# Communication_Management.net
KiCad netlist of a schematic drawn in Altium Designer
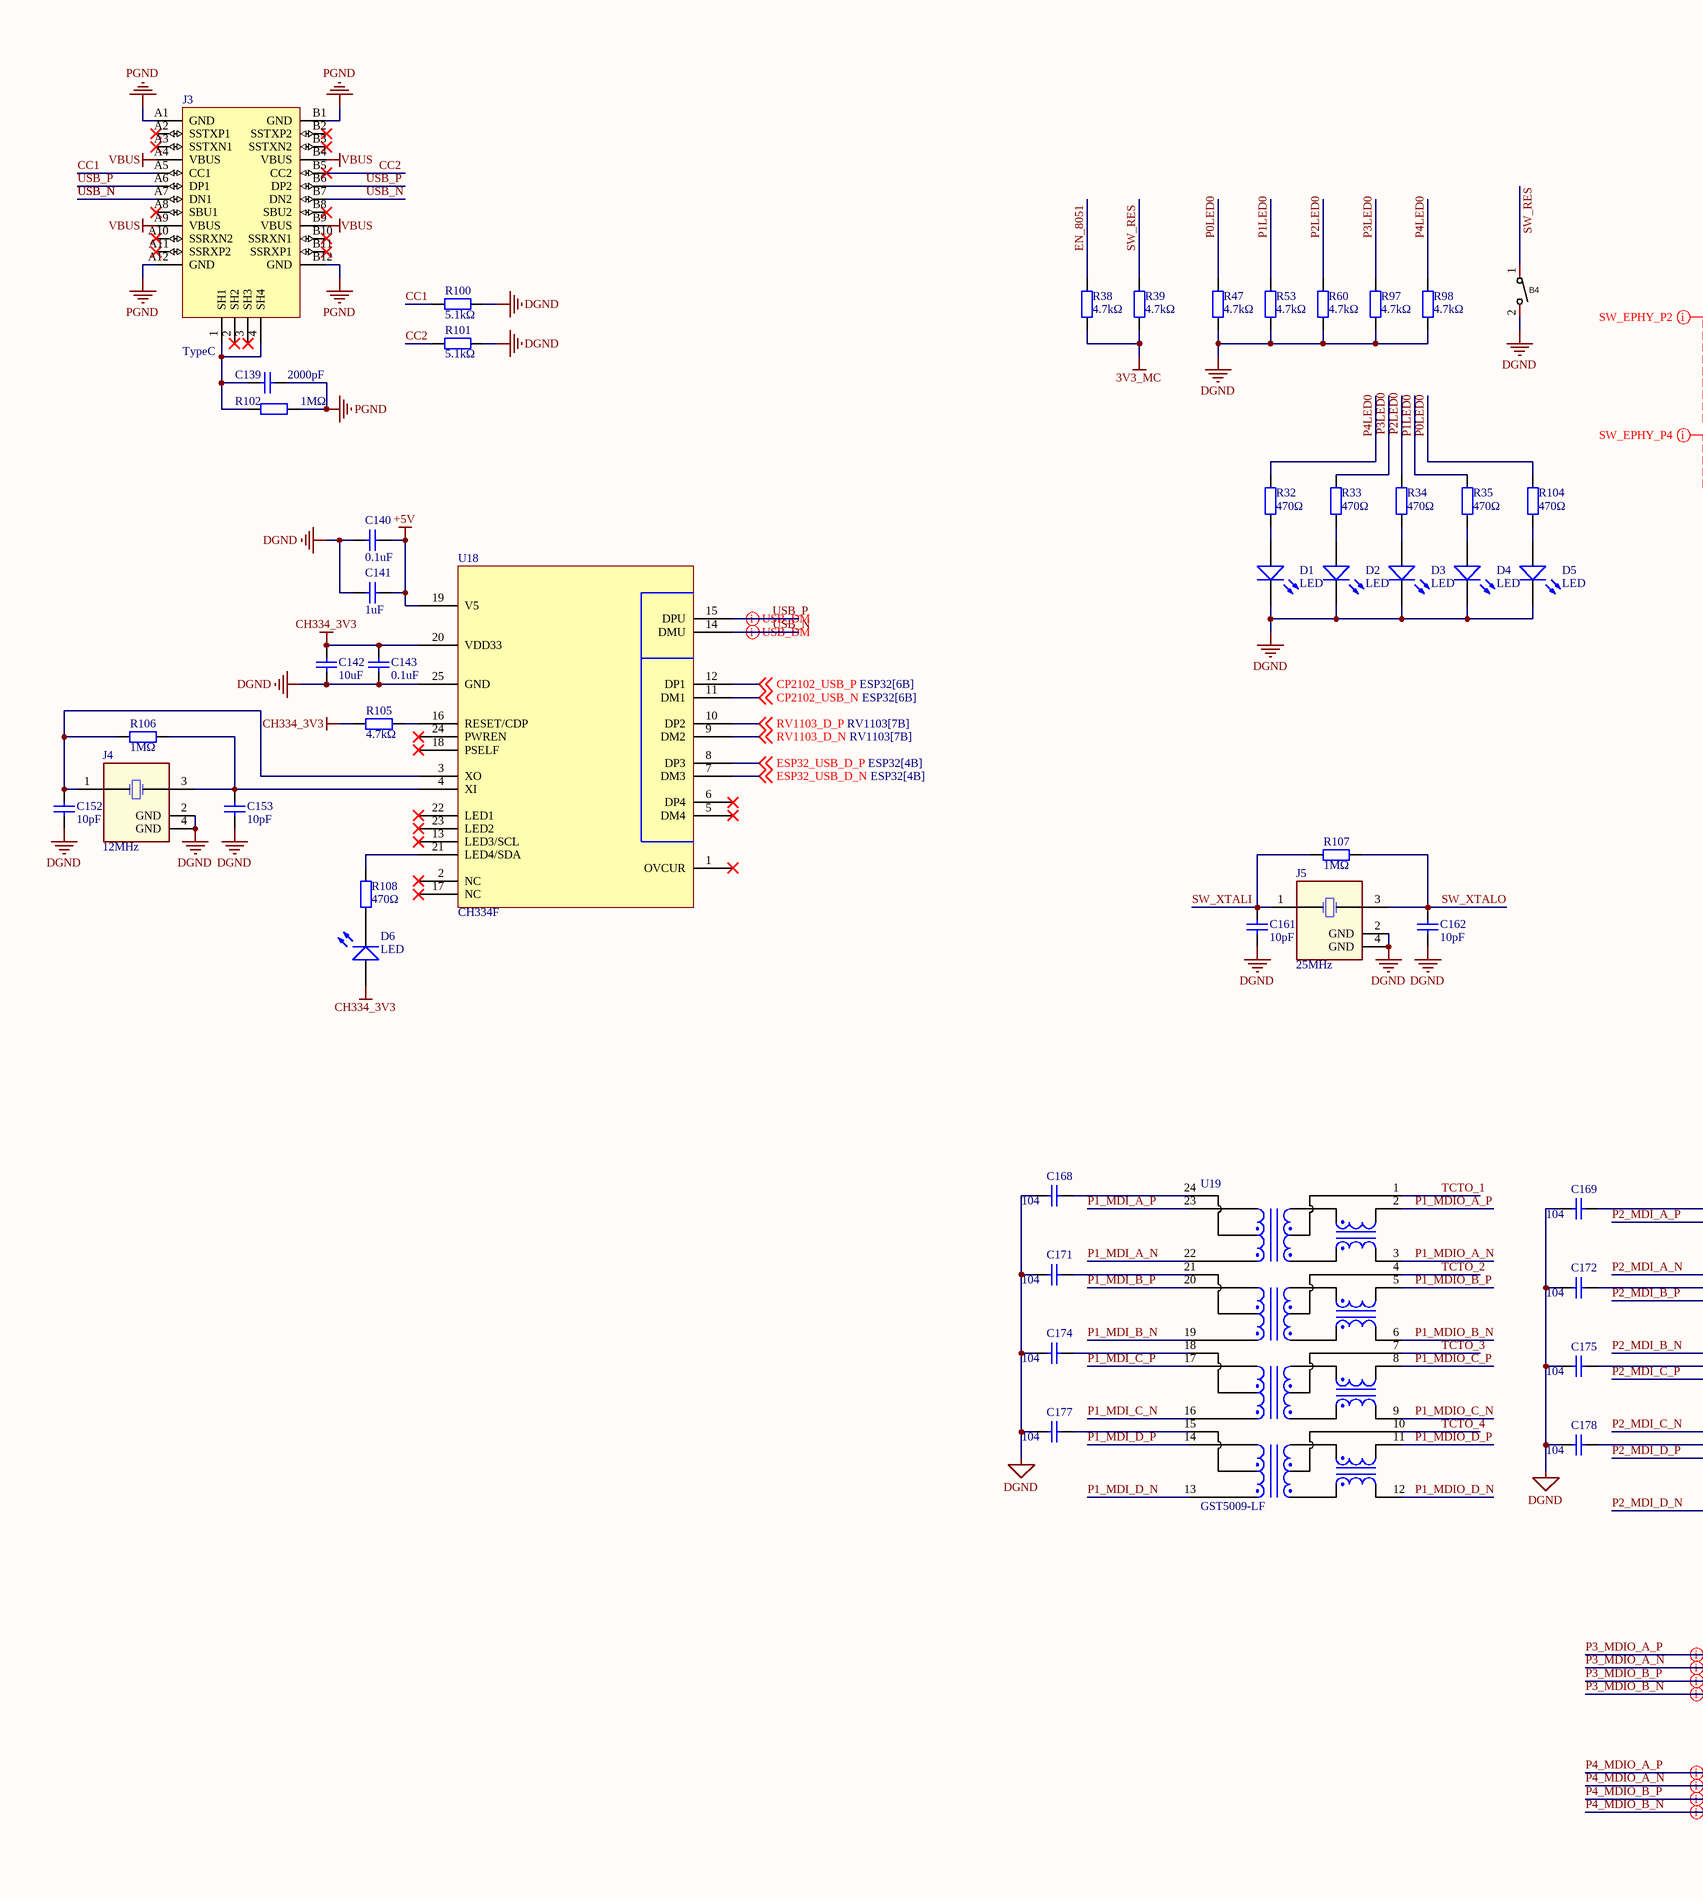
[diagram p0: Communication_Management.SchDoc, left]
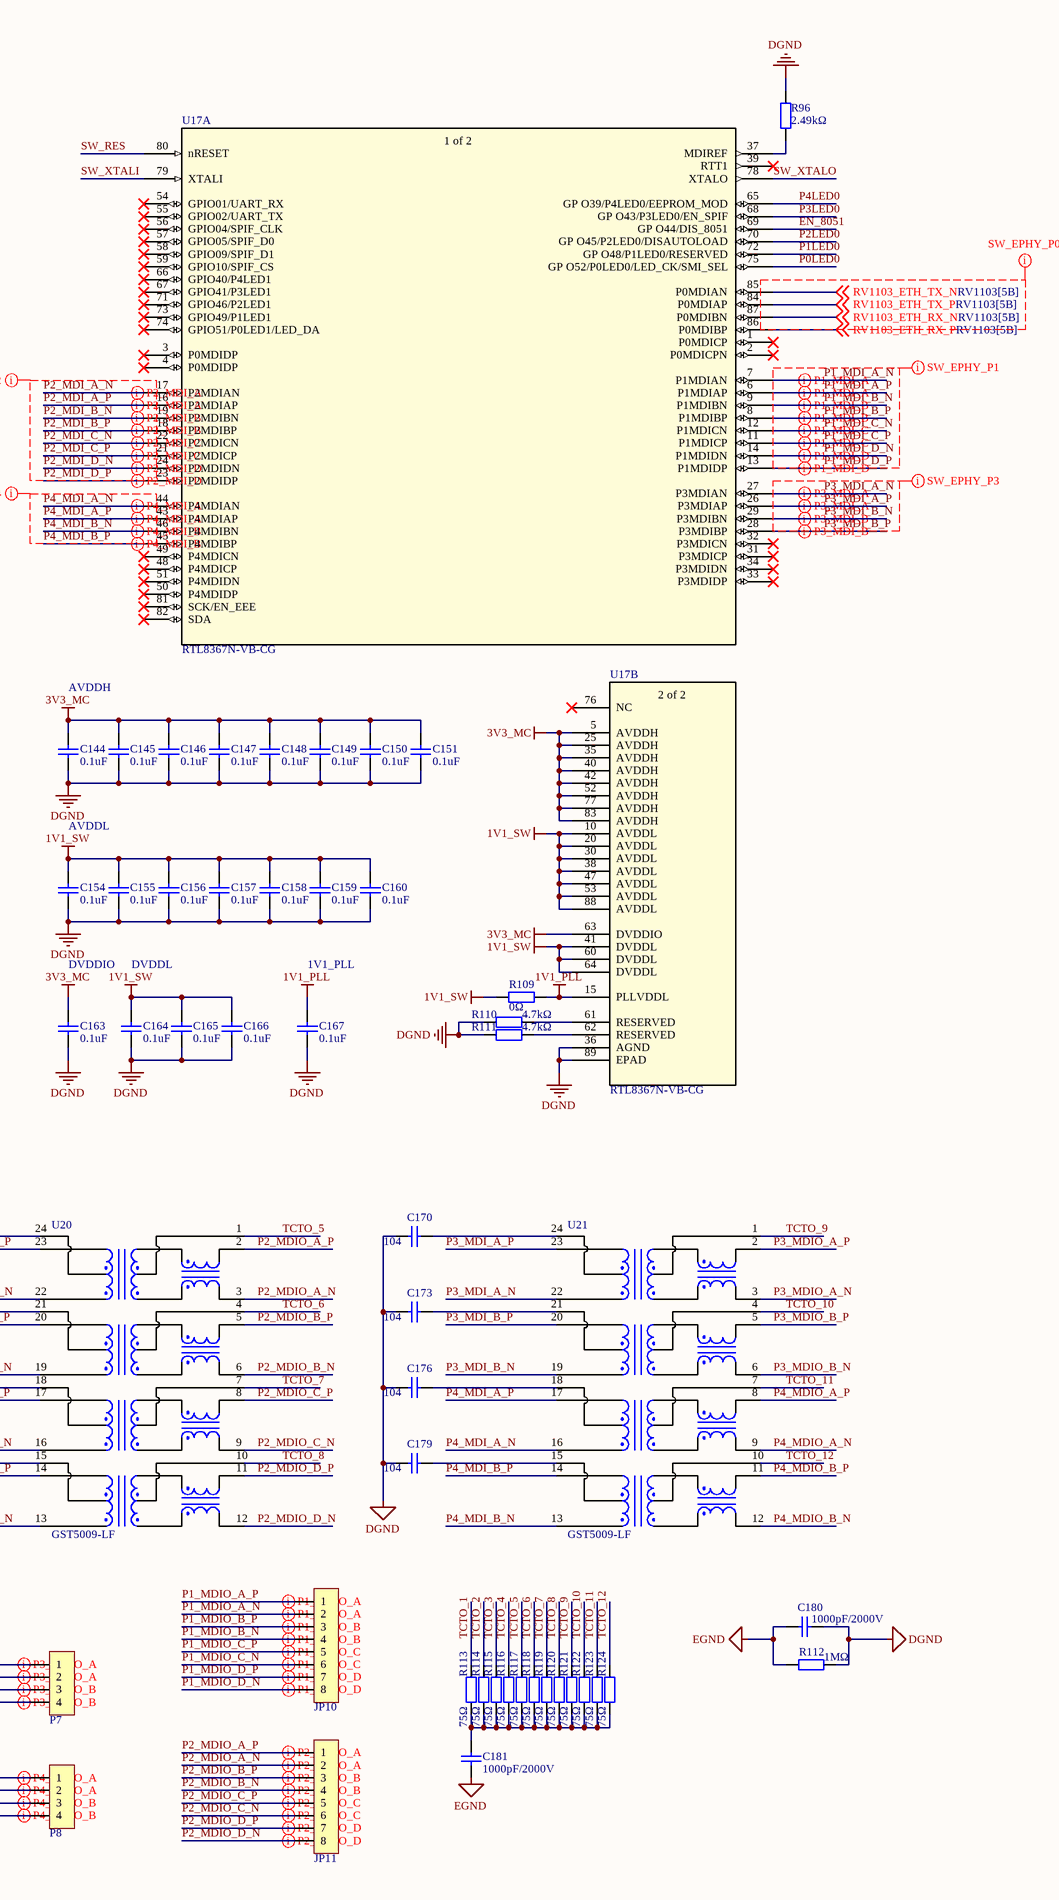
[diagram p1: Communication_Management.SchDoc, right]

(export (version "E")
  (design (tool "Eeschema 10.0.6"))
  (components
    (comp (ref "B4")
      (value "Bottom-2P-1Way")
      (footprint "SFerret:SW-SMD_L4.0-W2.9-LS5.0")
      (description "轻触按键")
      (fields (field (name "MANUFACTURER") "SHOU HAN(首韩)") (field (name "MANUFACTURER PART") "TS342A2P-WZ"))
      (libsource (lib "SFerret") (part "Bottom-2P-1Way"))
    )
    (comp (ref "C139")
      (value "2000pF")
      (footprint "1210_C")
      (description "贴片电容")
      (libsource (lib "SFerret") (part "SMT_Cap"))
    )
    (comp (ref "C140")
      (value "0.1uF")
      (footprint "0603_C")
      (description "贴片电容")
      (libsource (lib "SFerret") (part "SMT_Cap"))
    )
    (comp (ref "C141")
      (value "1uF")
      (footprint "0603_C")
      (description "贴片电容")
      (libsource (lib "SFerret") (part "SMT_Cap"))
    )
    (comp (ref "C142")
      (value "10uF")
      (footprint "0603_C")
      (description "贴片电容")
      (libsource (lib "SFerret") (part "SMT_Cap"))
    )
    (comp (ref "C143")
      (value "0.1uF")
      (footprint "0603_C")
      (description "贴片电容")
      (libsource (lib "SFerret") (part "SMT_Cap"))
    )
    (comp (ref "C144")
      (value "0.1uF")
      (footprint "0402_C")
      (description "贴片电容")
      (libsource (lib "SFerret") (part "SMT_Cap"))
    )
    (comp (ref "C145")
      (value "0.1uF")
      (footprint "0402_C")
      (description "贴片电容")
      (libsource (lib "SFerret") (part "SMT_Cap"))
    )
    (comp (ref "C146")
      (value "0.1uF")
      (footprint "0402_C")
      (description "贴片电容")
      (libsource (lib "SFerret") (part "SMT_Cap"))
    )
    (comp (ref "C147")
      (value "0.1uF")
      (footprint "0402_C")
      (description "贴片电容")
      (libsource (lib "SFerret") (part "SMT_Cap"))
    )
    (comp (ref "C148")
      (value "0.1uF")
      (footprint "0402_C")
      (description "贴片电容")
      (libsource (lib "SFerret") (part "SMT_Cap"))
    )
    (comp (ref "C149")
      (value "0.1uF")
      (footprint "0402_C")
      (description "贴片电容")
      (libsource (lib "SFerret") (part "SMT_Cap"))
    )
    (comp (ref "C150")
      (value "0.1uF")
      (footprint "0402_C")
      (description "贴片电容")
      (libsource (lib "SFerret") (part "SMT_Cap"))
    )
    (comp (ref "C151")
      (value "0.1uF")
      (footprint "0402_C")
      (description "贴片电容")
      (libsource (lib "SFerret") (part "SMT_Cap"))
    )
    (comp (ref "C152")
      (value "10pF")
      (footprint "0603_C")
      (description "贴片电容")
      (libsource (lib "SFerret") (part "SMT_Cap"))
    )
    (comp (ref "C153")
      (value "10pF")
      (footprint "0603_C")
      (description "贴片电容")
      (libsource (lib "SFerret") (part "SMT_Cap"))
    )
    (comp (ref "C154")
      (value "0.1uF")
      (footprint "0402_C")
      (description "贴片电容")
      (libsource (lib "SFerret") (part "SMT_Cap"))
    )
    (comp (ref "C155")
      (value "0.1uF")
      (footprint "0402_C")
      (description "贴片电容")
      (libsource (lib "SFerret") (part "SMT_Cap"))
    )
    (comp (ref "C156")
      (value "0.1uF")
      (footprint "0402_C")
      (description "贴片电容")
      (libsource (lib "SFerret") (part "SMT_Cap"))
    )
    (comp (ref "C157")
      (value "0.1uF")
      (footprint "0402_C")
      (description "贴片电容")
      (libsource (lib "SFerret") (part "SMT_Cap"))
    )
    (comp (ref "C158")
      (value "0.1uF")
      (footprint "0402_C")
      (description "贴片电容")
      (libsource (lib "SFerret") (part "SMT_Cap"))
    )
    (comp (ref "C159")
      (value "0.1uF")
      (footprint "0402_C")
      (description "贴片电容")
      (libsource (lib "SFerret") (part "SMT_Cap"))
    )
    (comp (ref "C160")
      (value "0.1uF")
      (footprint "0402_C")
      (description "贴片电容")
      (libsource (lib "SFerret") (part "SMT_Cap"))
    )
    (comp (ref "C161")
      (value "10pF")
      (footprint "0402_C")
      (description "贴片电容")
      (libsource (lib "SFerret") (part "SMT_Cap"))
    )
    (comp (ref "C162")
      (value "10pF")
      (footprint "0402_C")
      (description "贴片电容")
      (libsource (lib "SFerret") (part "SMT_Cap"))
    )
    (comp (ref "C163")
      (value "0.1uF")
      (footprint "0402_C")
      (description "贴片电容")
      (libsource (lib "SFerret") (part "SMT_Cap"))
    )
    (comp (ref "C164")
      (value "0.1uF")
      (footprint "0402_C")
      (description "贴片电容")
      (libsource (lib "SFerret") (part "SMT_Cap"))
    )
    (comp (ref "C165")
      (value "0.1uF")
      (footprint "0402_C")
      (description "贴片电容")
      (libsource (lib "SFerret") (part "SMT_Cap"))
    )
    (comp (ref "C166")
      (value "0.1uF")
      (footprint "0402_C")
      (description "贴片电容")
      (libsource (lib "SFerret") (part "SMT_Cap"))
    )
    (comp (ref "C167")
      (value "0.1uF")
      (footprint "0402_C")
      (description "贴片电容")
      (libsource (lib "SFerret") (part "SMT_Cap"))
    )
    (comp (ref "C168")
      (value "104")
      (footprint "0402_C")
      (description "贴片电容")
      (libsource (lib "SFerret") (part "SMT_Cap"))
    )
    (comp (ref "C169")
      (value "104")
      (footprint "0402_C")
      (description "贴片电容")
      (libsource (lib "SFerret") (part "SMT_Cap"))
    )
    (comp (ref "C170")
      (value "104")
      (footprint "0402_C")
      (description "贴片电容")
      (libsource (lib "SFerret") (part "SMT_Cap"))
    )
    (comp (ref "C171")
      (value "104")
      (footprint "0402_C")
      (description "贴片电容")
      (libsource (lib "SFerret") (part "SMT_Cap"))
    )
    (comp (ref "C172")
      (value "104")
      (footprint "0402_C")
      (description "贴片电容")
      (libsource (lib "SFerret") (part "SMT_Cap"))
    )
    (comp (ref "C173")
      (value "104")
      (footprint "0402_C")
      (description "贴片电容")
      (libsource (lib "SFerret") (part "SMT_Cap"))
    )
    (comp (ref "C174")
      (value "104")
      (footprint "0402_C")
      (description "贴片电容")
      (libsource (lib "SFerret") (part "SMT_Cap"))
    )
    (comp (ref "C175")
      (value "104")
      (footprint "0402_C")
      (description "贴片电容")
      (libsource (lib "SFerret") (part "SMT_Cap"))
    )
    (comp (ref "C176")
      (value "104")
      (footprint "0402_C")
      (description "贴片电容")
      (libsource (lib "SFerret") (part "SMT_Cap"))
    )
    (comp (ref "C177")
      (value "104")
      (footprint "0402_C")
      (description "贴片电容")
      (libsource (lib "SFerret") (part "SMT_Cap"))
    )
    (comp (ref "C178")
      (value "104")
      (footprint "0402_C")
      (description "贴片电容")
      (libsource (lib "SFerret") (part "SMT_Cap"))
    )
    (comp (ref "C179")
      (value "104")
      (footprint "0402_C")
      (description "贴片电容")
      (libsource (lib "SFerret") (part "SMT_Cap"))
    )
    (comp (ref "C180")
      (value "1000pF/2000V")
      (footprint "1210_C")
      (description "贴片电容")
      (libsource (lib "SFerret") (part "SMT_Cap"))
    )
    (comp (ref "C181")
      (value "1000pF/2000V")
      (footprint "1210_C")
      (description "贴片电容")
      (libsource (lib "SFerret") (part "SMT_Cap"))
    )
    (comp (ref "D1")
      (value "LED")
      (footprint "0603_LED")
      (description "发光二极管")
      (libsource (lib "SFerret") (part "LED"))
    )
    (comp (ref "D2")
      (value "LED")
      (footprint "0603_LED")
      (description "发光二极管")
      (libsource (lib "SFerret") (part "LED"))
    )
    (comp (ref "D3")
      (value "LED")
      (footprint "0603_LED")
      (description "发光二极管")
      (libsource (lib "SFerret") (part "LED"))
    )
    (comp (ref "D4")
      (value "LED")
      (footprint "0603_LED")
      (description "发光二极管")
      (libsource (lib "SFerret") (part "LED"))
    )
    (comp (ref "D5")
      (value "LED")
      (footprint "0603_LED")
      (description "发光二极管")
      (libsource (lib "SFerret") (part "LED"))
    )
    (comp (ref "D6")
      (value "LED")
      (footprint "0603_LED")
      (description "发光二极管")
      (libsource (lib "SFerret") (part "LED"))
    )
    (comp (ref "J3") (value "TypeC") (footprint "TYPE-C 16P") (libsource (lib "集大电协1.5") (part "TypeC")))
    (comp (ref "J4")
      (value "12MHz")
      (footprint "SMD-2520_4P")
      (libsource (lib "SFerret") (part "Oscillator_SMT_4P"))
    )
    (comp (ref "J5")
      (value "25MHz")
      (footprint "SMD-2520_4P")
      (libsource (lib "SFerret") (part "Oscillator_SMT_4P"))
    )
    (comp (ref "JP10")
      (value "HDR-1X8")
      (footprint "MX 1.25-LI-8P")
      (description "8P接插件")
      (libsource (lib "5.0 - 接插件-脚距1.25") (part "Header 8"))
    )
    (comp (ref "JP11")
      (value "HDR-1X8")
      (footprint "MX 1.25-LI-8P")
      (description "8P接插件")
      (libsource (lib "5.0 - 接插件-脚距1.25") (part "Header 8"))
    )
    (comp (ref "P7")
      (value "HDR-1X4")
      (footprint "MX 1.25-LI-4P")
      (description "4P接插件")
      (libsource (lib "5.0 - 接插件-脚距1.25") (part "Header 4"))
    )
    (comp (ref "P8")
      (value "HDR-1X4")
      (footprint "MX 1.25-LI-4P")
      (description "4P接插件")
      (libsource (lib "5.0 - 接插件-脚距1.25") (part "Header 4"))
    )
    (comp (ref "R32")
      (value "470Ω")
      (footprint "0603_R")
      (description "贴片电阻")
      (libsource (lib "SFerret") (part "SMT_Res"))
    )
    (comp (ref "R33")
      (value "470Ω")
      (footprint "0603_R")
      (description "贴片电阻")
      (libsource (lib "SFerret") (part "SMT_Res"))
    )
    (comp (ref "R34")
      (value "470Ω")
      (footprint "0603_R")
      (description "贴片电阻")
      (libsource (lib "SFerret") (part "SMT_Res"))
    )
    (comp (ref "R35")
      (value "470Ω")
      (footprint "0603_R")
      (description "贴片电阻")
      (libsource (lib "SFerret") (part "SMT_Res"))
    )
    (comp (ref "R38")
      (value "4.7kΩ")
      (footprint "0402_R")
      (description "贴片电阻")
      (libsource (lib "") (part "SMT_Res_3"))
    )
    (comp (ref "R39")
      (value "4.7kΩ")
      (footprint "0402_R")
      (description "贴片电阻")
      (libsource (lib "") (part "SMT_Res_3"))
    )
    (comp (ref "R47")
      (value "4.7kΩ")
      (footprint "0402_R")
      (description "贴片电阻")
      (libsource (lib "SFerret") (part "SMT_Res"))
    )
    (comp (ref "R53")
      (value "4.7kΩ")
      (footprint "0402_R")
      (description "贴片电阻")
      (libsource (lib "SFerret") (part "SMT_Res"))
    )
    (comp (ref "R60")
      (value "4.7kΩ")
      (footprint "0402_R")
      (description "贴片电阻")
      (libsource (lib "SFerret") (part "SMT_Res"))
    )
    (comp (ref "R96")
      (value "2.49kΩ")
      (footprint "0402_R")
      (description "贴片电阻")
      (libsource (lib "SFerret") (part "SMT_Res"))
    )
    (comp (ref "R97")
      (value "4.7kΩ")
      (footprint "0402_R")
      (description "贴片电阻")
      (libsource (lib "SFerret") (part "SMT_Res"))
    )
    (comp (ref "R98")
      (value "4.7kΩ")
      (footprint "0402_R")
      (description "贴片电阻")
      (libsource (lib "SFerret") (part "SMT_Res"))
    )
    (comp (ref "R100")
      (value "5.1kΩ")
      (footprint "0603_R")
      (description "贴片电阻")
      (libsource (lib "") (part "SMT_Res_2"))
    )
    (comp (ref "R101")
      (value "5.1kΩ")
      (footprint "0603_R")
      (description "贴片电阻")
      (libsource (lib "") (part "SMT_Res_2"))
    )
    (comp (ref "R102")
      (value "1MΩ")
      (footprint "1206_R")
      (description "贴片电阻")
      (libsource (lib "") (part "SMT_Res_1"))
    )
    (comp (ref "R104")
      (value "470Ω")
      (footprint "0603_R")
      (description "贴片电阻")
      (libsource (lib "SFerret") (part "SMT_Res"))
    )
    (comp (ref "R105")
      (value "4.7kΩ")
      (footprint "0603_R")
      (description "贴片电阻")
      (libsource (lib "") (part "SMT_Res_1"))
    )
    (comp (ref "R106")
      (value "1MΩ")
      (footprint "0603_R")
      (description "贴片电阻")
      (libsource (lib "") (part "SMT_Res_1"))
    )
    (comp (ref "R107")
      (value "1MΩ")
      (footprint "0603_R")
      (description "贴片电阻")
      (libsource (lib "") (part "SMT_Res_1"))
    )
    (comp (ref "R108")
      (value "470Ω")
      (footprint "0603_R")
      (description "贴片电阻")
      (libsource (lib "SFerret") (part "SMT_Res"))
    )
    (comp (ref "R109")
      (value "0Ω")
      (footprint "0402_R")
      (description "贴片电阻")
      (libsource (lib "") (part "SMT_Res_1"))
    )
    (comp (ref "R110")
      (value "4.7kΩ")
      (footprint "0402_R")
      (description "贴片电阻")
      (libsource (lib "") (part "SMT_Res_1"))
    )
    (comp (ref "R111")
      (value "4.7kΩ")
      (footprint "0402_R")
      (description "贴片电阻")
      (libsource (lib "") (part "SMT_Res_1"))
    )
    (comp (ref "R112")
      (value "1MΩ")
      (footprint "1206_R")
      (description "贴片电阻")
      (libsource (lib "") (part "SMT_Res_1"))
    )
    (comp (ref "R113")
      (value "75Ω")
      (footprint "0402_R")
      (description "贴片电阻")
      (libsource (lib "SFerret") (part "SMT_Res"))
    )
    (comp (ref "R114")
      (value "75Ω")
      (footprint "0402_R")
      (description "贴片电阻")
      (libsource (lib "SFerret") (part "SMT_Res"))
    )
    (comp (ref "R115")
      (value "75Ω")
      (footprint "0402_R")
      (description "贴片电阻")
      (libsource (lib "SFerret") (part "SMT_Res"))
    )
    (comp (ref "R116")
      (value "75Ω")
      (footprint "0402_R")
      (description "贴片电阻")
      (libsource (lib "SFerret") (part "SMT_Res"))
    )
    (comp (ref "R117")
      (value "75Ω")
      (footprint "0402_R")
      (description "贴片电阻")
      (libsource (lib "SFerret") (part "SMT_Res"))
    )
    (comp (ref "R118")
      (value "75Ω")
      (footprint "0402_R")
      (description "贴片电阻")
      (libsource (lib "SFerret") (part "SMT_Res"))
    )
    (comp (ref "R119")
      (value "75Ω")
      (footprint "0402_R")
      (description "贴片电阻")
      (libsource (lib "SFerret") (part "SMT_Res"))
    )
    (comp (ref "R120")
      (value "75Ω")
      (footprint "0402_R")
      (description "贴片电阻")
      (libsource (lib "SFerret") (part "SMT_Res"))
    )
    (comp (ref "R121")
      (value "75Ω")
      (footprint "0402_R")
      (description "贴片电阻")
      (libsource (lib "SFerret") (part "SMT_Res"))
    )
    (comp (ref "R122")
      (value "75Ω")
      (footprint "0402_R")
      (description "贴片电阻")
      (libsource (lib "SFerret") (part "SMT_Res"))
    )
    (comp (ref "R123")
      (value "75Ω")
      (footprint "0402_R")
      (description "贴片电阻")
      (libsource (lib "SFerret") (part "SMT_Res"))
    )
    (comp (ref "R124")
      (value "75Ω")
      (footprint "0402_R")
      (description "贴片电阻")
      (libsource (lib "SFerret") (part "SMT_Res"))
    )
    (comp (ref "U17")
      (value "RTL8367N-VB-CG")
      (footprint "QFN88-10x10MM")
      (description "SINGLE-CHIP 5-PORT 10/100/1000M \r\nSWITCH CONTROLLER")
      (fields (field (name "COPYRIGHT") "Copyright (C) 2023 Ultra Librarian. All rights reserved."))
      (libsource (lib "SFerret") (part "RTL8367N-VB-CG"))
    )
    (comp (ref "U18")
      (value "CH334F")
      (footprint "QFN50P400X400X80_HS-25N")
      (description "USB hub controller")
      (libsource (lib "SFerret") (part "CH334F"))
    )
    (comp (ref "U19")
      (value "GST5009-LF")
      (footprint "SOP100P1000X400-24N")
      (description "Network")
      (libsource (lib "SFerret") (part "GST5009-LF"))
    )
    (comp (ref "U20")
      (value "GST5009-LF")
      (footprint "SOP100P1000X400-24N")
      (description "Network")
      (libsource (lib "SFerret") (part "GST5009-LF"))
    )
    (comp (ref "U21")
      (value "GST5009-LF")
      (footprint "SOP100P1000X400-24N")
      (description "Network")
      (libsource (lib "SFerret") (part "GST5009-LF"))
    )
  )
  (nets
    (net (code "1") (name "+5V") (class "Default")
      (node (ref "C140") (pin "2") (pinfunction "2_2") (pintype "passive"))
      (node (ref "C141") (pin "2") (pinfunction "2_2") (pintype "passive"))
      (node (ref "U18") (pin "19") (pinfunction "V5_19") (pintype "passive"))
    )
    (net (code "2") (name "/CC1") (class "Default")
      (node (ref "J3") (pin "A5") (pinfunction "CC1_A5") (pintype "bidirectional"))
      (node (ref "R100") (pin "2") (pinfunction "2_2") (pintype "passive"))
    )
    (net (code "3") (name "/CC2") (class "Default")
      (node (ref "J3") (pin "B5") (pinfunction "CC2_B5") (pintype "bidirectional"))
      (node (ref "R101") (pin "2") (pinfunction "2_2") (pintype "passive"))
    )
    (net (code "4") (name "/EN_8051") (class "Default")
      (node (ref "R38") (pin "1") (pinfunction "1_1") (pintype "passive"))
      (node (ref "U17") (pin "69") (pinfunction "GP_O44/DIS_8051_69") (pintype "bidirectional"))
    )
    (net (code "5") (name "/P0LED0") (class "Default")
      (node (ref "R104") (pin "2") (pinfunction "2_2") (pintype "passive"))
      (node (ref "R47") (pin "2") (pinfunction "2_2") (pintype "passive"))
      (node (ref "U17") (pin "75") (pinfunction "GP_O52/P0LED0/LED_CK/SMI_SEL_75") (pintype "bidirectional"))
    )
    (net (code "6") (name "/P1LED0") (class "Default")
      (node (ref "R35") (pin "2") (pinfunction "2_2") (pintype "passive"))
      (node (ref "R53") (pin "2") (pinfunction "2_2") (pintype "passive"))
      (node (ref "U17") (pin "72") (pinfunction "GP_O48/P1LED0/RESERVED_72") (pintype "bidirectional"))
    )
    (net (code "7") (name "/P1_MDIO_A_N") (class "Default")
      (node (ref "JP10") (pin "2") (pinfunction "2_2") (pintype "passive"))
      (node (ref "U19") (pin "3") (pinfunction "16_3") (pintype "passive"))
    )
    (net (code "8") (name "/P1_MDIO_A_P") (class "Default")
      (node (ref "JP10") (pin "1") (pinfunction "1_1") (pintype "passive"))
      (node (ref "U19") (pin "2") (pinfunction "2_2") (pintype "passive"))
    )
    (net (code "9") (name "/P1_MDIO_B_N") (class "Default")
      (node (ref "JP10") (pin "4") (pinfunction "4_4") (pintype "passive"))
      (node (ref "U19") (pin "6") (pinfunction "6_6") (pintype "passive"))
    )
    (net (code "10") (name "/P1_MDIO_B_P") (class "Default")
      (node (ref "JP10") (pin "3") (pinfunction "3_3") (pintype "passive"))
      (node (ref "U19") (pin "5") (pinfunction "5_5") (pintype "passive"))
    )
    (net (code "11") (name "/P1_MDIO_C_N") (class "Default")
      (node (ref "JP10") (pin "6") (pinfunction "6_6") (pintype "passive"))
      (node (ref "U19") (pin "9") (pinfunction "9_9") (pintype "passive"))
    )
    (net (code "12") (name "/P1_MDIO_C_P") (class "Default")
      (node (ref "JP10") (pin "5") (pinfunction "5_5") (pintype "passive"))
      (node (ref "U19") (pin "8") (pinfunction "8_8") (pintype "passive"))
    )
    (net (code "13") (name "/P1_MDIO_D_N") (class "Default")
      (node (ref "JP10") (pin "8") (pinfunction "8_8") (pintype "passive"))
      (node (ref "U19") (pin "12") (pinfunction "12_12") (pintype "passive"))
    )
    (net (code "14") (name "/P1_MDIO_D_P") (class "Default")
      (node (ref "JP10") (pin "7") (pinfunction "7_7") (pintype "passive"))
      (node (ref "U19") (pin "11") (pinfunction "11_11") (pintype "passive"))
    )
    (net (code "15") (name "/P1_MDI_A_N") (class "Default")
      (node (ref "U17") (pin "7") (pinfunction "P1MDIAN_7") (pintype "bidirectional"))
      (node (ref "U19") (pin "22") (pinfunction "22_22") (pintype "passive"))
    )
    (net (code "16") (name "/P1_MDI_A_P") (class "Default")
      (node (ref "U17") (pin "6") (pinfunction "P1MDIAP_6") (pintype "bidirectional"))
      (node (ref "U19") (pin "23") (pinfunction "23_23") (pintype "passive"))
    )
    (net (code "17") (name "/P1_MDI_B_N") (class "Default")
      (node (ref "U17") (pin "9") (pinfunction "P1MDIBN_9") (pintype "bidirectional"))
      (node (ref "U19") (pin "19") (pinfunction "19_19") (pintype "passive"))
    )
    (net (code "18") (name "/P1_MDI_B_P") (class "Default")
      (node (ref "U17") (pin "8") (pinfunction "P1MDIBP_8") (pintype "bidirectional"))
      (node (ref "U19") (pin "20") (pinfunction "20_20") (pintype "passive"))
    )
    (net (code "19") (name "/P1_MDI_C_N") (class "Default")
      (node (ref "U17") (pin "12") (pinfunction "P1MDICN_12") (pintype "bidirectional"))
      (node (ref "U19") (pin "16") (pinfunction "16_16") (pintype "passive"))
    )
    (net (code "20") (name "/P1_MDI_C_P") (class "Default")
      (node (ref "U17") (pin "11") (pinfunction "P1MDICP_11") (pintype "bidirectional"))
      (node (ref "U19") (pin "17") (pinfunction "17_17") (pintype "passive"))
    )
    (net (code "21") (name "/P1_MDI_D_N") (class "Default")
      (node (ref "U17") (pin "14") (pinfunction "P1MDIDN_14") (pintype "bidirectional"))
      (node (ref "U19") (pin "13") (pinfunction "13_13") (pintype "passive"))
    )
    (net (code "22") (name "/P1_MDI_D_P") (class "Default")
      (node (ref "U17") (pin "13") (pinfunction "P1MDIDP_13") (pintype "bidirectional"))
      (node (ref "U19") (pin "14") (pinfunction "14_14") (pintype "passive"))
    )
    (net (code "23") (name "/P2LED0") (class "Default")
      (node (ref "R34") (pin "2") (pinfunction "2_2") (pintype "passive"))
      (node (ref "R60") (pin "2") (pinfunction "2_2") (pintype "passive"))
      (node (ref "U17") (pin "70") (pinfunction "GP_O45/P2LED0/DISAUTOLOAD_70") (pintype "bidirectional"))
    )
    (net (code "24") (name "/P2_MDIO_A_N") (class "Default")
      (node (ref "JP11") (pin "2") (pinfunction "2_2") (pintype "passive"))
      (node (ref "U20") (pin "3") (pinfunction "16_3") (pintype "passive"))
    )
    (net (code "25") (name "/P2_MDIO_A_P") (class "Default")
      (node (ref "JP11") (pin "1") (pinfunction "1_1") (pintype "passive"))
      (node (ref "U20") (pin "2") (pinfunction "2_2") (pintype "passive"))
    )
    (net (code "26") (name "/P2_MDIO_B_N") (class "Default")
      (node (ref "JP11") (pin "4") (pinfunction "4_4") (pintype "passive"))
      (node (ref "U20") (pin "6") (pinfunction "6_6") (pintype "passive"))
    )
    (net (code "27") (name "/P2_MDIO_B_P") (class "Default")
      (node (ref "JP11") (pin "3") (pinfunction "3_3") (pintype "passive"))
      (node (ref "U20") (pin "5") (pinfunction "5_5") (pintype "passive"))
    )
    (net (code "28") (name "/P2_MDIO_C_N") (class "Default")
      (node (ref "JP11") (pin "6") (pinfunction "6_6") (pintype "passive"))
      (node (ref "U20") (pin "9") (pinfunction "9_9") (pintype "passive"))
    )
    (net (code "29") (name "/P2_MDIO_C_P") (class "Default")
      (node (ref "JP11") (pin "5") (pinfunction "5_5") (pintype "passive"))
      (node (ref "U20") (pin "8") (pinfunction "8_8") (pintype "passive"))
    )
    (net (code "30") (name "/P2_MDIO_D_N") (class "Default")
      (node (ref "JP11") (pin "8") (pinfunction "8_8") (pintype "passive"))
      (node (ref "U20") (pin "12") (pinfunction "12_12") (pintype "passive"))
    )
    (net (code "31") (name "/P2_MDIO_D_P") (class "Default")
      (node (ref "JP11") (pin "7") (pinfunction "7_7") (pintype "passive"))
      (node (ref "U20") (pin "11") (pinfunction "11_11") (pintype "passive"))
    )
    (net (code "32") (name "/P2_MDI_A_N") (class "Default")
      (node (ref "U17") (pin "17") (pinfunction "P2MDIAN_17") (pintype "bidirectional"))
      (node (ref "U20") (pin "22") (pinfunction "22_22") (pintype "passive"))
    )
    (net (code "33") (name "/P2_MDI_A_P") (class "Default")
      (node (ref "U17") (pin "16") (pinfunction "P2MDIAP_16") (pintype "bidirectional"))
      (node (ref "U20") (pin "23") (pinfunction "23_23") (pintype "passive"))
    )
    (net (code "34") (name "/P2_MDI_B_N") (class "Default")
      (node (ref "U17") (pin "19") (pinfunction "P2MDIBN_19") (pintype "bidirectional"))
      (node (ref "U20") (pin "19") (pinfunction "19_19") (pintype "passive"))
    )
    (net (code "35") (name "/P2_MDI_B_P") (class "Default")
      (node (ref "U17") (pin "18") (pinfunction "P2MDIBP_18") (pintype "bidirectional"))
      (node (ref "U20") (pin "20") (pinfunction "20_20") (pintype "passive"))
    )
    (net (code "36") (name "/P2_MDI_C_N") (class "Default")
      (node (ref "U17") (pin "22") (pinfunction "P2MDICN_22") (pintype "bidirectional"))
      (node (ref "U20") (pin "16") (pinfunction "16_16") (pintype "passive"))
    )
    (net (code "37") (name "/P2_MDI_C_P") (class "Default")
      (node (ref "U17") (pin "21") (pinfunction "P2MDICP_21") (pintype "bidirectional"))
      (node (ref "U20") (pin "17") (pinfunction "17_17") (pintype "passive"))
    )
    (net (code "38") (name "/P2_MDI_D_N") (class "Default")
      (node (ref "U17") (pin "24") (pinfunction "P2MDIDN_24") (pintype "bidirectional"))
      (node (ref "U20") (pin "13") (pinfunction "13_13") (pintype "passive"))
    )
    (net (code "39") (name "/P2_MDI_D_P") (class "Default")
      (node (ref "U17") (pin "23") (pinfunction "P2MDIDP_23") (pintype "bidirectional"))
      (node (ref "U20") (pin "14") (pinfunction "14_14") (pintype "passive"))
    )
    (net (code "40") (name "/P3LED0") (class "Default")
      (node (ref "R33") (pin "2") (pinfunction "2_2") (pintype "passive"))
      (node (ref "R97") (pin "2") (pinfunction "2_2") (pintype "passive"))
      (node (ref "U17") (pin "68") (pinfunction "GP_O43/P3LED0/EN_SPIF_68") (pintype "bidirectional"))
    )
    (net (code "41") (name "/P3_MDIO_A_N") (class "Default")
      (node (ref "P7") (pin "2") (pinfunction "2_2") (pintype "passive"))
      (node (ref "U21") (pin "3") (pinfunction "16_3") (pintype "passive"))
    )
    (net (code "42") (name "/P3_MDIO_A_P") (class "Default")
      (node (ref "P7") (pin "1") (pinfunction "1_1") (pintype "passive"))
      (node (ref "U21") (pin "2") (pinfunction "2_2") (pintype "passive"))
    )
    (net (code "43") (name "/P3_MDIO_B_N") (class "Default")
      (node (ref "P7") (pin "4") (pinfunction "4_4") (pintype "passive"))
      (node (ref "U21") (pin "6") (pinfunction "6_6") (pintype "passive"))
    )
    (net (code "44") (name "/P3_MDIO_B_P") (class "Default")
      (node (ref "P7") (pin "3") (pinfunction "3_3") (pintype "passive"))
      (node (ref "U21") (pin "5") (pinfunction "5_5") (pintype "passive"))
    )
    (net (code "45") (name "/P3_MDI_A_N") (class "Default")
      (node (ref "U17") (pin "27") (pinfunction "P3MDIAN_27") (pintype "bidirectional"))
      (node (ref "U21") (pin "22") (pinfunction "22_22") (pintype "passive"))
    )
    (net (code "46") (name "/P3_MDI_A_P") (class "Default")
      (node (ref "U17") (pin "26") (pinfunction "P3MDIAP_26") (pintype "bidirectional"))
      (node (ref "U21") (pin "23") (pinfunction "23_23") (pintype "passive"))
    )
    (net (code "47") (name "/P3_MDI_B_N") (class "Default")
      (node (ref "U17") (pin "29") (pinfunction "P3MDIBN_29") (pintype "bidirectional"))
      (node (ref "U21") (pin "19") (pinfunction "19_19") (pintype "passive"))
    )
    (net (code "48") (name "/P3_MDI_B_P") (class "Default")
      (node (ref "U17") (pin "28") (pinfunction "P3MDIBP_28") (pintype "bidirectional"))
      (node (ref "U21") (pin "20") (pinfunction "20_20") (pintype "passive"))
    )
    (net (code "49") (name "/P4LED0") (class "Default")
      (node (ref "R32") (pin "2") (pinfunction "2_2") (pintype "passive"))
      (node (ref "R98") (pin "2") (pinfunction "2_2") (pintype "passive"))
      (node (ref "U17") (pin "65") (pinfunction "GP_O39/P4LED0/EEPROM_MOD_65") (pintype "bidirectional"))
    )
    (net (code "50") (name "/P4_MDIO_A_N") (class "Default")
      (node (ref "P8") (pin "2") (pinfunction "2_2") (pintype "passive"))
      (node (ref "U21") (pin "9") (pinfunction "9_9") (pintype "passive"))
    )
    (net (code "51") (name "/P4_MDIO_A_P") (class "Default")
      (node (ref "P8") (pin "1") (pinfunction "1_1") (pintype "passive"))
      (node (ref "U21") (pin "8") (pinfunction "8_8") (pintype "passive"))
    )
    (net (code "52") (name "/P4_MDIO_B_N") (class "Default")
      (node (ref "P8") (pin "4") (pinfunction "4_4") (pintype "passive"))
      (node (ref "U21") (pin "12") (pinfunction "12_12") (pintype "passive"))
    )
    (net (code "53") (name "/P4_MDIO_B_P") (class "Default")
      (node (ref "P8") (pin "3") (pinfunction "3_3") (pintype "passive"))
      (node (ref "U21") (pin "11") (pinfunction "11_11") (pintype "passive"))
    )
    (net (code "54") (name "/P4_MDI_A_N") (class "Default")
      (node (ref "U17") (pin "44") (pinfunction "P4MDIAN_44") (pintype "bidirectional"))
      (node (ref "U21") (pin "16") (pinfunction "16_16") (pintype "passive"))
    )
    (net (code "55") (name "/P4_MDI_A_P") (class "Default")
      (node (ref "U17") (pin "43") (pinfunction "P4MDIAP_43") (pintype "bidirectional"))
      (node (ref "U21") (pin "17") (pinfunction "17_17") (pintype "passive"))
    )
    (net (code "56") (name "/P4_MDI_B_N") (class "Default")
      (node (ref "U17") (pin "46") (pinfunction "P4MDIBN_46") (pintype "bidirectional"))
      (node (ref "U21") (pin "13") (pinfunction "13_13") (pintype "passive"))
    )
    (net (code "57") (name "/P4_MDI_B_P") (class "Default")
      (node (ref "U17") (pin "45") (pinfunction "P4MDIBP_45") (pintype "bidirectional"))
      (node (ref "U21") (pin "14") (pinfunction "14_14") (pintype "passive"))
    )
    (net (code "58") (name "/SW_RES") (class "Default")
      (node (ref "B4") (pin "1") (pinfunction "1_1") (pintype "passive"))
      (node (ref "R39") (pin "1") (pinfunction "1_1") (pintype "passive"))
      (node (ref "U17") (pin "80") (pinfunction "nRESET_80") (pintype "input"))
    )
    (net (code "59") (name "/SW_XTALI") (class "Default")
      (node (ref "C161") (pin "2") (pinfunction "2_2") (pintype "passive"))
      (node (ref "J5") (pin "1") (pinfunction "OSC1_1") (pintype "passive"))
      (node (ref "R107") (pin "1") (pinfunction "1_1") (pintype "passive"))
      (node (ref "U17") (pin "79") (pinfunction "XTALI_79") (pintype "input"))
    )
    (net (code "60") (name "/SW_XTALO") (class "Default")
      (node (ref "C162") (pin "2") (pinfunction "2_2") (pintype "passive"))
      (node (ref "J5") (pin "3") (pinfunction "OSC2_3") (pintype "passive"))
      (node (ref "R107") (pin "2") (pinfunction "2_2") (pintype "passive"))
      (node (ref "U17") (pin "78") (pinfunction "XTALO_78") (pintype "output"))
    )
    (net (code "61") (name "/TCTO_1") (class "Default")
      (node (ref "R113") (pin "2") (pinfunction "2_2") (pintype "passive"))
      (node (ref "U19") (pin "1") (pinfunction "1_1") (pintype "passive"))
    )
    (net (code "62") (name "/TCTO_2") (class "Default")
      (node (ref "R114") (pin "2") (pinfunction "2_2") (pintype "passive"))
      (node (ref "U19") (pin "4") (pinfunction "4_4") (pintype "passive"))
    )
    (net (code "63") (name "/TCTO_3") (class "Default")
      (node (ref "R115") (pin "2") (pinfunction "2_2") (pintype "passive"))
      (node (ref "U19") (pin "7") (pinfunction "7_7") (pintype "passive"))
    )
    (net (code "64") (name "/TCTO_4") (class "Default")
      (node (ref "R116") (pin "2") (pinfunction "2_2") (pintype "passive"))
      (node (ref "U19") (pin "10") (pinfunction "10_10") (pintype "passive"))
    )
    (net (code "65") (name "/TCTO_5") (class "Default")
      (node (ref "R117") (pin "2") (pinfunction "2_2") (pintype "passive"))
      (node (ref "U20") (pin "1") (pinfunction "1_1") (pintype "passive"))
    )
    (net (code "66") (name "/TCTO_6") (class "Default")
      (node (ref "R118") (pin "2") (pinfunction "2_2") (pintype "passive"))
      (node (ref "U20") (pin "4") (pinfunction "4_4") (pintype "passive"))
    )
    (net (code "67") (name "/TCTO_7") (class "Default")
      (node (ref "R119") (pin "2") (pinfunction "2_2") (pintype "passive"))
      (node (ref "U20") (pin "7") (pinfunction "7_7") (pintype "passive"))
    )
    (net (code "68") (name "/TCTO_8") (class "Default")
      (node (ref "R120") (pin "2") (pinfunction "2_2") (pintype "passive"))
      (node (ref "U20") (pin "10") (pinfunction "10_10") (pintype "passive"))
    )
    (net (code "69") (name "/TCTO_9") (class "Default")
      (node (ref "R121") (pin "2") (pinfunction "2_2") (pintype "passive"))
      (node (ref "U21") (pin "1") (pinfunction "1_1") (pintype "passive"))
    )
    (net (code "70") (name "/TCTO_10") (class "Default")
      (node (ref "R122") (pin "2") (pinfunction "2_2") (pintype "passive"))
      (node (ref "U21") (pin "4") (pinfunction "4_4") (pintype "passive"))
    )
    (net (code "71") (name "/TCTO_11") (class "Default")
      (node (ref "R123") (pin "2") (pinfunction "2_2") (pintype "passive"))
      (node (ref "U21") (pin "7") (pinfunction "7_7") (pintype "passive"))
    )
    (net (code "72") (name "/TCTO_12") (class "Default")
      (node (ref "R124") (pin "2") (pinfunction "2_2") (pintype "passive"))
      (node (ref "U21") (pin "10") (pinfunction "10_10") (pintype "passive"))
    )
    (net (code "73") (name "/USB_N") (class "Default")
      (node (ref "J3") (pin "A7") (pinfunction "DN1_A7") (pintype "bidirectional"))
      (node (ref "J3") (pin "B7") (pinfunction "DN2_B7") (pintype "bidirectional"))
      (node (ref "U18") (pin "14") (pinfunction "DMU_14") (pintype "passive"))
    )
    (net (code "74") (name "/USB_P") (class "Default")
      (node (ref "J3") (pin "A6") (pinfunction "DP1_A6") (pintype "bidirectional"))
      (node (ref "J3") (pin "B6") (pinfunction "DP2_B6") (pintype "bidirectional"))
      (node (ref "U18") (pin "15") (pinfunction "DPU_15") (pintype "passive"))
    )
    (net (code "75") (name "1V1_PLL") (class "Default")
      (node (ref "C167") (pin "2") (pinfunction "2_2") (pintype "passive"))
      (node (ref "R109") (pin "2") (pinfunction "2_2") (pintype "passive"))
      (node (ref "U17") (pin "15") (pinfunction "PLLVDDL_15") (pintype "power_in"))
    )
    (net (code "76") (name "1V1_SW") (class "Default")
      (node (ref "C154") (pin "2") (pinfunction "2_2") (pintype "passive"))
      (node (ref "C155") (pin "2") (pinfunction "2_2") (pintype "passive"))
      (node (ref "C156") (pin "2") (pinfunction "2_2") (pintype "passive"))
      (node (ref "C157") (pin "2") (pinfunction "2_2") (pintype "passive"))
      (node (ref "C158") (pin "2") (pinfunction "2_2") (pintype "passive"))
      (node (ref "C159") (pin "2") (pinfunction "2_2") (pintype "passive"))
      (node (ref "C160") (pin "2") (pinfunction "2_2") (pintype "passive"))
      (node (ref "C164") (pin "2") (pinfunction "2_2") (pintype "passive"))
      (node (ref "C165") (pin "2") (pinfunction "2_2") (pintype "passive"))
      (node (ref "C166") (pin "2") (pinfunction "2_2") (pintype "passive"))
      (node (ref "R109") (pin "1") (pinfunction "1_1") (pintype "passive"))
      (node (ref "U17") (pin "10") (pinfunction "AVDDL_10") (pintype "power_in"))
      (node (ref "U17") (pin "20") (pinfunction "AVDDL_20") (pintype "power_in"))
      (node (ref "U17") (pin "30") (pinfunction "AVDDL_30") (pintype "power_in"))
      (node (ref "U17") (pin "38") (pinfunction "AVDDL_38") (pintype "power_in"))
      (node (ref "U17") (pin "41") (pinfunction "DVDDL_41") (pintype "power_in"))
      (node (ref "U17") (pin "47") (pinfunction "AVDDL_47") (pintype "power_in"))
      (node (ref "U17") (pin "53") (pinfunction "AVDDL_53") (pintype "power_in"))
      (node (ref "U17") (pin "60") (pinfunction "DVDDL_60") (pintype "power_in"))
      (node (ref "U17") (pin "64") (pinfunction "DVDDL_64") (pintype "power_in"))
      (node (ref "U17") (pin "88") (pinfunction "AVDDL_88") (pintype "power_in"))
    )
    (net (code "77") (name "3V3_MC") (class "Default")
      (node (ref "C144") (pin "2") (pinfunction "2_2") (pintype "passive"))
      (node (ref "C145") (pin "2") (pinfunction "2_2") (pintype "passive"))
      (node (ref "C146") (pin "2") (pinfunction "2_2") (pintype "passive"))
      (node (ref "C147") (pin "2") (pinfunction "2_2") (pintype "passive"))
      (node (ref "C148") (pin "2") (pinfunction "2_2") (pintype "passive"))
      (node (ref "C149") (pin "2") (pinfunction "2_2") (pintype "passive"))
      (node (ref "C150") (pin "2") (pinfunction "2_2") (pintype "passive"))
      (node (ref "C151") (pin "2") (pinfunction "2_2") (pintype "passive"))
      (node (ref "C163") (pin "2") (pinfunction "2_2") (pintype "passive"))
      (node (ref "R38") (pin "2") (pinfunction "2_2") (pintype "passive"))
      (node (ref "R39") (pin "2") (pinfunction "2_2") (pintype "passive"))
      (node (ref "U17") (pin "25") (pinfunction "AVDDH_25") (pintype "power_in"))
      (node (ref "U17") (pin "35") (pinfunction "AVDDH_35") (pintype "power_in"))
      (node (ref "U17") (pin "40") (pinfunction "AVDDH_40") (pintype "power_in"))
      (node (ref "U17") (pin "42") (pinfunction "AVDDH_42") (pintype "power_in"))
      (node (ref "U17") (pin "5") (pinfunction "AVDDH_5") (pintype "power_in"))
      (node (ref "U17") (pin "52") (pinfunction "AVDDH_52") (pintype "power_in"))
      (node (ref "U17") (pin "63") (pinfunction "DVDDIO_63") (pintype "power_in"))
      (node (ref "U17") (pin "77") (pinfunction "AVDDH_77") (pintype "power_in"))
      (node (ref "U17") (pin "83") (pinfunction "AVDDH_83") (pintype "power_in"))
    )
    (net (code "78") (name "CH334_3V3") (class "Default")
      (node (ref "C142") (pin "2") (pinfunction "2_2") (pintype "passive"))
      (node (ref "C143") (pin "2") (pinfunction "2_2") (pintype "passive"))
      (node (ref "D6") (pin "A") (pinfunction "A_A") (pintype "passive"))
      (node (ref "R105") (pin "1") (pinfunction "1_1") (pintype "passive"))
      (node (ref "U18") (pin "20") (pinfunction "VDD33_20") (pintype "passive"))
    )
    (net (code "79") (name "CP2102_USB_N") (class "Default")
      (node (ref "U18") (pin "11") (pinfunction "DM1_11") (pintype "passive"))
    )
    (net (code "80") (name "CP2102_USB_P") (class "Default")
      (node (ref "U18") (pin "12") (pinfunction "DP1_12") (pintype "passive"))
    )
    (net (code "81") (name "DGND") (class "Default")
      (node (ref "B4") (pin "2") (pinfunction "2_2") (pintype "passive"))
      (node (ref "C140") (pin "1") (pinfunction "1_1") (pintype "passive"))
      (node (ref "C141") (pin "1") (pinfunction "1_1") (pintype "passive"))
      (node (ref "C142") (pin "1") (pinfunction "1_1") (pintype "passive"))
      (node (ref "C143") (pin "1") (pinfunction "1_1") (pintype "passive"))
      (node (ref "C144") (pin "1") (pinfunction "1_1") (pintype "passive"))
      (node (ref "C145") (pin "1") (pinfunction "1_1") (pintype "passive"))
      (node (ref "C146") (pin "1") (pinfunction "1_1") (pintype "passive"))
      (node (ref "C147") (pin "1") (pinfunction "1_1") (pintype "passive"))
      (node (ref "C148") (pin "1") (pinfunction "1_1") (pintype "passive"))
      (node (ref "C149") (pin "1") (pinfunction "1_1") (pintype "passive"))
      (node (ref "C150") (pin "1") (pinfunction "1_1") (pintype "passive"))
      (node (ref "C151") (pin "1") (pinfunction "1_1") (pintype "passive"))
      (node (ref "C152") (pin "1") (pinfunction "1_1") (pintype "passive"))
      (node (ref "C153") (pin "1") (pinfunction "1_1") (pintype "passive"))
      (node (ref "C154") (pin "1") (pinfunction "1_1") (pintype "passive"))
      (node (ref "C155") (pin "1") (pinfunction "1_1") (pintype "passive"))
      (node (ref "C156") (pin "1") (pinfunction "1_1") (pintype "passive"))
      (node (ref "C157") (pin "1") (pinfunction "1_1") (pintype "passive"))
      (node (ref "C158") (pin "1") (pinfunction "1_1") (pintype "passive"))
      (node (ref "C159") (pin "1") (pinfunction "1_1") (pintype "passive"))
      (node (ref "C160") (pin "1") (pinfunction "1_1") (pintype "passive"))
      (node (ref "C161") (pin "1") (pinfunction "1_1") (pintype "passive"))
      (node (ref "C162") (pin "1") (pinfunction "1_1") (pintype "passive"))
      (node (ref "C163") (pin "1") (pinfunction "1_1") (pintype "passive"))
      (node (ref "C164") (pin "1") (pinfunction "1_1") (pintype "passive"))
      (node (ref "C165") (pin "1") (pinfunction "1_1") (pintype "passive"))
      (node (ref "C166") (pin "1") (pinfunction "1_1") (pintype "passive"))
      (node (ref "C167") (pin "1") (pinfunction "1_1") (pintype "passive"))
      (node (ref "C168") (pin "2") (pinfunction "2_2") (pintype "passive"))
      (node (ref "C169") (pin "2") (pinfunction "2_2") (pintype "passive"))
      (node (ref "C170") (pin "2") (pinfunction "2_2") (pintype "passive"))
      (node (ref "C171") (pin "2") (pinfunction "2_2") (pintype "passive"))
      (node (ref "C172") (pin "2") (pinfunction "2_2") (pintype "passive"))
      (node (ref "C173") (pin "2") (pinfunction "2_2") (pintype "passive"))
      (node (ref "C174") (pin "2") (pinfunction "2_2") (pintype "passive"))
      (node (ref "C175") (pin "2") (pinfunction "2_2") (pintype "passive"))
      (node (ref "C176") (pin "2") (pinfunction "2_2") (pintype "passive"))
      (node (ref "C177") (pin "2") (pinfunction "2_2") (pintype "passive"))
      (node (ref "C178") (pin "2") (pinfunction "2_2") (pintype "passive"))
      (node (ref "C179") (pin "2") (pinfunction "2_2") (pintype "passive"))
      (node (ref "C180") (pin "1") (pinfunction "1_1") (pintype "passive"))
      (node (ref "D1") (pin "K") (pinfunction "K_K") (pintype "passive"))
      (node (ref "D2") (pin "K") (pinfunction "K_K") (pintype "passive"))
      (node (ref "D3") (pin "K") (pinfunction "K_K") (pintype "passive"))
      (node (ref "D4") (pin "K") (pinfunction "K_K") (pintype "passive"))
      (node (ref "D5") (pin "K") (pinfunction "K_K") (pintype "passive"))
      (node (ref "J4") (pin "2") (pinfunction "GND_2") (pintype "passive"))
      (node (ref "J4") (pin "4") (pinfunction "GND_4") (pintype "passive"))
      (node (ref "J5") (pin "2") (pinfunction "GND_2") (pintype "passive"))
      (node (ref "J5") (pin "4") (pinfunction "GND_4") (pintype "passive"))
      (node (ref "R100") (pin "1") (pinfunction "1_1") (pintype "passive"))
      (node (ref "R101") (pin "1") (pinfunction "1_1") (pintype "passive"))
      (node (ref "R110") (pin "1") (pinfunction "1_1") (pintype "passive"))
      (node (ref "R111") (pin "1") (pinfunction "1_1") (pintype "passive"))
      (node (ref "R112") (pin "2") (pinfunction "2_2") (pintype "passive"))
      (node (ref "R47") (pin "1") (pinfunction "1_1") (pintype "passive"))
      (node (ref "R53") (pin "1") (pinfunction "1_1") (pintype "passive"))
      (node (ref "R60") (pin "1") (pinfunction "1_1") (pintype "passive"))
      (node (ref "R96") (pin "2") (pinfunction "2_2") (pintype "passive"))
      (node (ref "R97") (pin "1") (pinfunction "1_1") (pintype "passive"))
      (node (ref "R98") (pin "1") (pinfunction "1_1") (pintype "passive"))
      (node (ref "U17") (pin "36") (pinfunction "AGND_36") (pintype "power_in"))
      (node (ref "U17") (pin "89") (pinfunction "EPAD_89") (pintype "power_in"))
      (node (ref "U18") (pin "25") (pinfunction "GND_25") (pintype "passive"))
    )
    (net (code "82") (name "EGND") (class "Default")
      (node (ref "C180") (pin "2") (pinfunction "2_2") (pintype "passive"))
      (node (ref "C181") (pin "1") (pinfunction "1_1") (pintype "passive"))
      (node (ref "R112") (pin "1") (pinfunction "1_1") (pintype "passive"))
    )
    (net (code "83") (name "ESP32_USB_D_N") (class "Default")
      (node (ref "U18") (pin "7") (pinfunction "DM3_7") (pintype "passive"))
    )
    (net (code "84") (name "ESP32_USB_D_P") (class "Default")
      (node (ref "U18") (pin "8") (pinfunction "DP3_8") (pintype "passive"))
    )
    (net (code "85") (name "Net-(C168-Pad1)") (class "Default")
      (node (ref "C168") (pin "1") (pinfunction "1_1") (pintype "passive"))
      (node (ref "U19") (pin "24") (pinfunction "24_24") (pintype "passive"))
    )
    (net (code "86") (name "Net-(C169-Pad1)") (class "Default")
      (node (ref "C169") (pin "1") (pinfunction "1_1") (pintype "passive"))
      (node (ref "U20") (pin "24") (pinfunction "24_24") (pintype "passive"))
    )
    (net (code "87") (name "Net-(C170-Pad1)") (class "Default")
      (node (ref "C170") (pin "1") (pinfunction "1_1") (pintype "passive"))
      (node (ref "U21") (pin "24") (pinfunction "24_24") (pintype "passive"))
    )
    (net (code "88") (name "Net-(C171-Pad1)") (class "Default")
      (node (ref "C171") (pin "1") (pinfunction "1_1") (pintype "passive"))
      (node (ref "U19") (pin "21") (pinfunction "21_21") (pintype "passive"))
    )
    (net (code "89") (name "Net-(C172-Pad1)") (class "Default")
      (node (ref "C172") (pin "1") (pinfunction "1_1") (pintype "passive"))
      (node (ref "U20") (pin "21") (pinfunction "21_21") (pintype "passive"))
    )
    (net (code "90") (name "Net-(C173-Pad1)") (class "Default")
      (node (ref "C173") (pin "1") (pinfunction "1_1") (pintype "passive"))
      (node (ref "U21") (pin "21") (pinfunction "21_21") (pintype "passive"))
    )
    (net (code "91") (name "Net-(C174-Pad1)") (class "Default")
      (node (ref "C174") (pin "1") (pinfunction "1_1") (pintype "passive"))
      (node (ref "U19") (pin "18") (pinfunction "18_18") (pintype "passive"))
    )
    (net (code "92") (name "Net-(C175-Pad1)") (class "Default")
      (node (ref "C175") (pin "1") (pinfunction "1_1") (pintype "passive"))
      (node (ref "U20") (pin "18") (pinfunction "18_18") (pintype "passive"))
    )
    (net (code "93") (name "Net-(C176-Pad1)") (class "Default")
      (node (ref "C176") (pin "1") (pinfunction "1_1") (pintype "passive"))
      (node (ref "U21") (pin "18") (pinfunction "18_18") (pintype "passive"))
    )
    (net (code "94") (name "Net-(C177-Pad1)") (class "Default")
      (node (ref "C177") (pin "1") (pinfunction "1_1") (pintype "passive"))
      (node (ref "U19") (pin "15") (pinfunction "15_15") (pintype "passive"))
    )
    (net (code "95") (name "Net-(C178-Pad1)") (class "Default")
      (node (ref "C178") (pin "1") (pinfunction "1_1") (pintype "passive"))
      (node (ref "U20") (pin "15") (pinfunction "15_15") (pintype "passive"))
    )
    (net (code "96") (name "Net-(C179-Pad1)") (class "Default")
      (node (ref "C179") (pin "1") (pinfunction "1_1") (pintype "passive"))
      (node (ref "U21") (pin "15") (pinfunction "15_15") (pintype "passive"))
    )
    (net (code "97") (name "Net-(C181-Pad2)") (class "Default")
      (node (ref "C181") (pin "2") (pinfunction "2_2") (pintype "passive"))
      (node (ref "R113") (pin "1") (pinfunction "1_1") (pintype "passive"))
      (node (ref "R114") (pin "1") (pinfunction "1_1") (pintype "passive"))
      (node (ref "R115") (pin "1") (pinfunction "1_1") (pintype "passive"))
      (node (ref "R116") (pin "1") (pinfunction "1_1") (pintype "passive"))
      (node (ref "R117") (pin "1") (pinfunction "1_1") (pintype "passive"))
      (node (ref "R118") (pin "1") (pinfunction "1_1") (pintype "passive"))
      (node (ref "R119") (pin "1") (pinfunction "1_1") (pintype "passive"))
      (node (ref "R120") (pin "1") (pinfunction "1_1") (pintype "passive"))
      (node (ref "R121") (pin "1") (pinfunction "1_1") (pintype "passive"))
      (node (ref "R122") (pin "1") (pinfunction "1_1") (pintype "passive"))
      (node (ref "R123") (pin "1") (pinfunction "1_1") (pintype "passive"))
      (node (ref "R124") (pin "1") (pinfunction "1_1") (pintype "passive"))
    )
    (net (code "98") (name "Net-(D1-PadA)") (class "Default")
      (node (ref "D1") (pin "A") (pinfunction "A_A") (pintype "passive"))
      (node (ref "R32") (pin "1") (pinfunction "1_1") (pintype "passive"))
    )
    (net (code "99") (name "Net-(D2-PadA)") (class "Default")
      (node (ref "D2") (pin "A") (pinfunction "A_A") (pintype "passive"))
      (node (ref "R33") (pin "1") (pinfunction "1_1") (pintype "passive"))
    )
    (net (code "100") (name "Net-(D3-PadA)") (class "Default")
      (node (ref "D3") (pin "A") (pinfunction "A_A") (pintype "passive"))
      (node (ref "R34") (pin "1") (pinfunction "1_1") (pintype "passive"))
    )
    (net (code "101") (name "Net-(D4-PadA)") (class "Default")
      (node (ref "D4") (pin "A") (pinfunction "A_A") (pintype "passive"))
      (node (ref "R35") (pin "1") (pinfunction "1_1") (pintype "passive"))
    )
    (net (code "102") (name "Net-(D5-PadA)") (class "Default")
      (node (ref "D5") (pin "A") (pinfunction "A_A") (pintype "passive"))
      (node (ref "R104") (pin "1") (pinfunction "1_1") (pintype "passive"))
    )
    (net (code "103") (name "Net-(D6-PadK)") (class "Default")
      (node (ref "D6") (pin "K") (pinfunction "K_K") (pintype "passive"))
      (node (ref "R108") (pin "1") (pinfunction "1_1") (pintype "passive"))
    )
    (net (code "104") (name "Net-(J3-SH1)") (class "Default")
      (node (ref "C139") (pin "1") (pinfunction "1_1") (pintype "passive"))
      (node (ref "J3") (pin "1") (pinfunction "SH1_1") (pintype "power_in"))
      (node (ref "J3") (pin "4") (pinfunction "SH4_4") (pintype "power_in"))
      (node (ref "R102") (pin "1") (pinfunction "1_1") (pintype "passive"))
    )
    (net (code "105") (name "Net-(J4-OSC1)") (class "Default")
      (node (ref "C152") (pin "2") (pinfunction "2_2") (pintype "passive"))
      (node (ref "J4") (pin "1") (pinfunction "OSC1_1") (pintype "passive"))
      (node (ref "R106") (pin "1") (pinfunction "1_1") (pintype "passive"))
      (node (ref "U18") (pin "3") (pinfunction "XO_3") (pintype "passive"))
    )
    (net (code "106") (name "Net-(J4-OSC2)") (class "Default")
      (node (ref "C153") (pin "2") (pinfunction "2_2") (pintype "passive"))
      (node (ref "J4") (pin "3") (pinfunction "OSC2_3") (pintype "passive"))
      (node (ref "R106") (pin "2") (pinfunction "2_2") (pintype "passive"))
      (node (ref "U18") (pin "4") (pinfunction "XI_4") (pintype "passive"))
    )
    (net (code "107") (name "Net-(R110-Pad2)") (class "Default")
      (node (ref "R110") (pin "2") (pinfunction "2_2") (pintype "passive"))
      (node (ref "U17") (pin "61") (pinfunction "RESERVED_61") (pintype "power_in"))
    )
    (net (code "108") (name "Net-(R111-Pad2)") (class "Default")
      (node (ref "R111") (pin "2") (pinfunction "2_2") (pintype "passive"))
      (node (ref "U17") (pin "62") (pinfunction "RESERVED_62") (pintype "power_in"))
    )
    (net (code "109") (name "Net-(U17A-MDIREF)") (class "Default")
      (node (ref "R96") (pin "1") (pinfunction "1_1") (pintype "passive"))
      (node (ref "U17") (pin "37") (pinfunction "MDIREF_37") (pintype "output"))
    )
    (net (code "110") (name "Net-(U18-LED4{slash}SDA)") (class "Default")
      (node (ref "R108") (pin "2") (pinfunction "2_2") (pintype "passive"))
      (node (ref "U18") (pin "21") (pinfunction "LED4/SDA_21") (pintype "passive"))
    )
    (net (code "111") (name "Net-(U18-RESET{slash}CDP)") (class "Default")
      (node (ref "R105") (pin "2") (pinfunction "2_2") (pintype "passive"))
      (node (ref "U18") (pin "16") (pinfunction "RESET/CDP_16") (pintype "passive"))
    )
    (net (code "112") (name "PGND") (class "Default")
      (node (ref "C139") (pin "2") (pinfunction "2_2") (pintype "passive"))
      (node (ref "J3") (pin "A1") (pinfunction "GND_A1") (pintype "power_in"))
      (node (ref "J3") (pin "A12") (pinfunction "GND_A12") (pintype "power_in"))
      (node (ref "J3") (pin "B1") (pinfunction "GND_B1") (pintype "power_in"))
      (node (ref "J3") (pin "B12") (pinfunction "GND_B12") (pintype "power_in"))
      (node (ref "R102") (pin "2") (pinfunction "2_2") (pintype "passive"))
    )
    (net (code "113") (name "RV1103_D_N") (class "Default")
      (node (ref "U18") (pin "9") (pinfunction "DM2_9") (pintype "passive"))
    )
    (net (code "114") (name "RV1103_D_P") (class "Default")
      (node (ref "U18") (pin "10") (pinfunction "DP2_10") (pintype "passive"))
    )
    (net (code "115") (name "RV1103_ETH_RX_N") (class "Default")
      (node (ref "U17") (pin "87") (pinfunction "P0MDIBN_87") (pintype "bidirectional"))
    )
    (net (code "116") (name "RV1103_ETH_RX_P") (class "Default")
      (node (ref "U17") (pin "86") (pinfunction "P0MDIBP_86") (pintype "bidirectional"))
    )
    (net (code "117") (name "RV1103_ETH_TX_N") (class "Default")
      (node (ref "U17") (pin "85") (pinfunction "P0MDIAN_85") (pintype "bidirectional"))
    )
    (net (code "118") (name "RV1103_ETH_TX_P") (class "Default")
      (node (ref "U17") (pin "84") (pinfunction "P0MDIAP_84") (pintype "bidirectional"))
    )
    (net (code "119") (name "VBUS") (class "Default")
      (node (ref "J3") (pin "A4") (pinfunction "VBUS_A4") (pintype "power_in"))
      (node (ref "J3") (pin "A9") (pinfunction "VBUS_A9") (pintype "power_in"))
      (node (ref "J3") (pin "B4") (pinfunction "VBUS_B4") (pintype "power_in"))
      (node (ref "J3") (pin "B9") (pinfunction "VBUS_B9") (pintype "power_in"))
    )
    (net (code "120") (name "unconnected-(J3-SBU1-PadA8)") (class "Default")
      (node (ref "J3") (pin "A8") (pinfunction "SBU1_A8") (pintype "bidirectional+no_connect"))
    )
    (net (code "121") (name "unconnected-(J3-SBU2-PadB8)") (class "Default")
      (node (ref "J3") (pin "B8") (pinfunction "SBU2_B8") (pintype "bidirectional+no_connect"))
    )
    (net (code "122") (name "unconnected-(J3-SH2-Pad2)") (class "Default")
      (node (ref "J3") (pin "2") (pinfunction "SH2_2") (pintype "power_in+no_connect"))
    )
    (net (code "123") (name "unconnected-(J3-SH3-Pad3)") (class "Default")
      (node (ref "J3") (pin "3") (pinfunction "SH3_3") (pintype "power_in+no_connect"))
    )
    (net (code "124") (name "unconnected-(J3-SSRXN1-PadB10)") (class "Default")
      (node (ref "J3") (pin "B10") (pinfunction "SSRXN1_B10") (pintype "bidirectional+no_connect"))
    )
    (net (code "125") (name "unconnected-(J3-SSRXN2-PadA10)") (class "Default")
      (node (ref "J3") (pin "A10") (pinfunction "SSRXN2_A10") (pintype "bidirectional+no_connect"))
    )
    (net (code "126") (name "unconnected-(J3-SSRXP1-PadB11)") (class "Default")
      (node (ref "J3") (pin "B11") (pinfunction "SSRXP1_B11") (pintype "bidirectional+no_connect"))
    )
    (net (code "127") (name "unconnected-(J3-SSRXP2-PadA11)") (class "Default")
      (node (ref "J3") (pin "A11") (pinfunction "SSRXP2_A11") (pintype "bidirectional+no_connect"))
    )
    (net (code "128") (name "unconnected-(J3-SSTXN1-PadA3)") (class "Default")
      (node (ref "J3") (pin "A3") (pinfunction "SSTXN1_A3") (pintype "bidirectional+no_connect"))
    )
    (net (code "129") (name "unconnected-(J3-SSTXN2-PadB3)") (class "Default")
      (node (ref "J3") (pin "B3") (pinfunction "SSTXN2_B3") (pintype "bidirectional+no_connect"))
    )
    (net (code "130") (name "unconnected-(J3-SSTXP1-PadA2)") (class "Default")
      (node (ref "J3") (pin "A2") (pinfunction "SSTXP1_A2") (pintype "bidirectional+no_connect"))
    )
    (net (code "131") (name "unconnected-(J3-SSTXP2-PadB2)") (class "Default")
      (node (ref "J3") (pin "B2") (pinfunction "SSTXP2_B2") (pintype "bidirectional+no_connect"))
    )
    (net (code "132") (name "unconnected-(U17A-GPIO01{slash}UART_RX-Pad54)") (class "Default")
      (node (ref "U17") (pin "54") (pinfunction "GPIO01/UART_RX_54") (pintype "bidirectional+no_connect"))
    )
    (net (code "133") (name "unconnected-(U17A-GPIO02{slash}UART_TX-Pad55)") (class "Default")
      (node (ref "U17") (pin "55") (pinfunction "GPIO02/UART_TX_55") (pintype "bidirectional+no_connect"))
    )
    (net (code "134") (name "unconnected-(U17A-GPIO04{slash}SPIF_CLK-Pad56)") (class "Default")
      (node (ref "U17") (pin "56") (pinfunction "GPIO04/SPIF_CLK_56") (pintype "bidirectional+no_connect"))
    )
    (net (code "135") (name "unconnected-(U17A-GPIO05{slash}SPIF_D0-Pad57)") (class "Default")
      (node (ref "U17") (pin "57") (pinfunction "GPIO05/SPIF_D0_57") (pintype "bidirectional+no_connect"))
    )
    (net (code "136") (name "unconnected-(U17A-GPIO09{slash}SPIF_D1-Pad58)") (class "Default")
      (node (ref "U17") (pin "58") (pinfunction "GPIO09/SPIF_D1_58") (pintype "bidirectional+no_connect"))
    )
    (net (code "137") (name "unconnected-(U17A-GPIO10{slash}SPIF_CS-Pad59)") (class "Default")
      (node (ref "U17") (pin "59") (pinfunction "GPIO10/SPIF_CS_59") (pintype "bidirectional+no_connect"))
    )
    (net (code "138") (name "unconnected-(U17A-GPIO40{slash}P4LED1-Pad66)") (class "Default")
      (node (ref "U17") (pin "66") (pinfunction "GPIO40/P4LED1_66") (pintype "bidirectional+no_connect"))
    )
    (net (code "139") (name "unconnected-(U17A-GPIO41{slash}P3LED1-Pad67)") (class "Default")
      (node (ref "U17") (pin "67") (pinfunction "GPIO41/P3LED1_67") (pintype "bidirectional+no_connect"))
    )
    (net (code "140") (name "unconnected-(U17A-GPIO46{slash}P2LED1-Pad71)") (class "Default")
      (node (ref "U17") (pin "71") (pinfunction "GPIO46/P2LED1_71") (pintype "bidirectional+no_connect"))
    )
    (net (code "141") (name "unconnected-(U17A-GPIO49{slash}P1LED1-Pad73)") (class "Default")
      (node (ref "U17") (pin "73") (pinfunction "GPIO49/P1LED1_73") (pintype "bidirectional+no_connect"))
    )
    (net (code "142") (name "unconnected-(U17A-GPIO51{slash}P0LED1{slash}LED_DA-Pad74)") (class "Default")
      (node (ref "U17") (pin "74") (pinfunction "GPIO51/P0LED1/LED_DA_74") (pintype "bidirectional+no_connect"))
    )
    (net (code "143") (name "unconnected-(U17A-P0MDICP-Pad1)") (class "Default")
      (node (ref "U17") (pin "1") (pinfunction "P0MDICP_1") (pintype "bidirectional+no_connect"))
    )
    (net (code "144") (name "unconnected-(U17A-P0MDICPN-Pad2)") (class "Default")
      (node (ref "U17") (pin "2") (pinfunction "P0MDICPN_2") (pintype "bidirectional+no_connect"))
    )
    (net (code "145") (name "unconnected-(U17A-P0MDIDP-Pad3)") (class "Default")
      (node (ref "U17") (pin "3") (pinfunction "P0MDIDP_3") (pintype "bidirectional+no_connect"))
    )
    (net (code "146") (name "unconnected-(U17A-P0MDIDP-Pad4)") (class "Default")
      (node (ref "U17") (pin "4") (pinfunction "P0MDIDP_4") (pintype "bidirectional+no_connect"))
    )
    (net (code "147") (name "unconnected-(U17A-P3MDICN-Pad32)") (class "Default")
      (node (ref "U17") (pin "32") (pinfunction "P3MDICN_32") (pintype "bidirectional+no_connect"))
    )
    (net (code "148") (name "unconnected-(U17A-P3MDICP-Pad31)") (class "Default")
      (node (ref "U17") (pin "31") (pinfunction "P3MDICP_31") (pintype "bidirectional+no_connect"))
    )
    (net (code "149") (name "unconnected-(U17A-P3MDIDN-Pad34)") (class "Default")
      (node (ref "U17") (pin "34") (pinfunction "P3MDIDN_34") (pintype "bidirectional+no_connect"))
    )
    (net (code "150") (name "unconnected-(U17A-P3MDIDP-Pad33)") (class "Default")
      (node (ref "U17") (pin "33") (pinfunction "P3MDIDP_33") (pintype "bidirectional+no_connect"))
    )
    (net (code "151") (name "unconnected-(U17A-P4MDICN-Pad49)") (class "Default")
      (node (ref "U17") (pin "49") (pinfunction "P4MDICN_49") (pintype "bidirectional+no_connect"))
    )
    (net (code "152") (name "unconnected-(U17A-P4MDICP-Pad48)") (class "Default")
      (node (ref "U17") (pin "48") (pinfunction "P4MDICP_48") (pintype "bidirectional+no_connect"))
    )
    (net (code "153") (name "unconnected-(U17A-P4MDIDN-Pad51)") (class "Default")
      (node (ref "U17") (pin "51") (pinfunction "P4MDIDN_51") (pintype "bidirectional+no_connect"))
    )
    (net (code "154") (name "unconnected-(U17A-P4MDIDP-Pad50)") (class "Default")
      (node (ref "U17") (pin "50") (pinfunction "P4MDIDP_50") (pintype "bidirectional+no_connect"))
    )
    (net (code "155") (name "unconnected-(U17A-RTT1-Pad39)") (class "Default")
      (node (ref "U17") (pin "39") (pinfunction "RTT1_39") (pintype "output+no_connect"))
    )
    (net (code "156") (name "unconnected-(U17A-SCK{slash}EN_EEE-Pad81)") (class "Default")
      (node (ref "U17") (pin "81") (pinfunction "SCK/EN_EEE_81") (pintype "bidirectional+no_connect"))
    )
    (net (code "157") (name "unconnected-(U17A-SDA-Pad82)") (class "Default")
      (node (ref "U17") (pin "82") (pinfunction "SDA_82") (pintype "bidirectional+no_connect"))
    )
    (net (code "158") (name "unconnected-(U17B-NC-Pad76)") (class "Default")
      (node (ref "U17") (pin "76") (pinfunction "NC_76") (pintype "passive+no_connect"))
    )
    (net (code "159") (name "unconnected-(U18-DM4-Pad5)") (class "Default")
      (node (ref "U18") (pin "5") (pinfunction "DM4_5") (pintype "passive+no_connect"))
    )
    (net (code "160") (name "unconnected-(U18-DP4-Pad6)") (class "Default")
      (node (ref "U18") (pin "6") (pinfunction "DP4_6") (pintype "passive+no_connect"))
    )
    (net (code "161") (name "unconnected-(U18-LED1-Pad22)") (class "Default")
      (node (ref "U18") (pin "22") (pinfunction "LED1_22") (pintype "passive+no_connect"))
    )
    (net (code "162") (name "unconnected-(U18-LED2-Pad23)") (class "Default")
      (node (ref "U18") (pin "23") (pinfunction "LED2_23") (pintype "passive+no_connect"))
    )
    (net (code "163") (name "unconnected-(U18-LED3{slash}SCL-Pad13)") (class "Default")
      (node (ref "U18") (pin "13") (pinfunction "LED3/SCL_13") (pintype "passive+no_connect"))
    )
    (net (code "164") (name "unconnected-(U18-NC-Pad2)") (class "Default")
      (node (ref "U18") (pin "2") (pinfunction "NC_2") (pintype "passive+no_connect"))
    )
    (net (code "165") (name "unconnected-(U18-NC-Pad17)") (class "Default")
      (node (ref "U18") (pin "17") (pinfunction "NC_17") (pintype "passive+no_connect"))
    )
    (net (code "166") (name "unconnected-(U18-OVCUR-Pad1)") (class "Default")
      (node (ref "U18") (pin "1") (pinfunction "OVCUR_1") (pintype "passive+no_connect"))
    )
    (net (code "167") (name "unconnected-(U18-PSELF-Pad18)") (class "Default")
      (node (ref "U18") (pin "18") (pinfunction "PSELF_18") (pintype "passive+no_connect"))
    )
    (net (code "168") (name "unconnected-(U18-PWREN-Pad24)") (class "Default")
      (node (ref "U18") (pin "24") (pinfunction "PWREN_24") (pintype "passive+no_connect"))
    )
  )
)
